# AMP_1_2.net
KiCad netlist of a schematic drawn in EAGLE
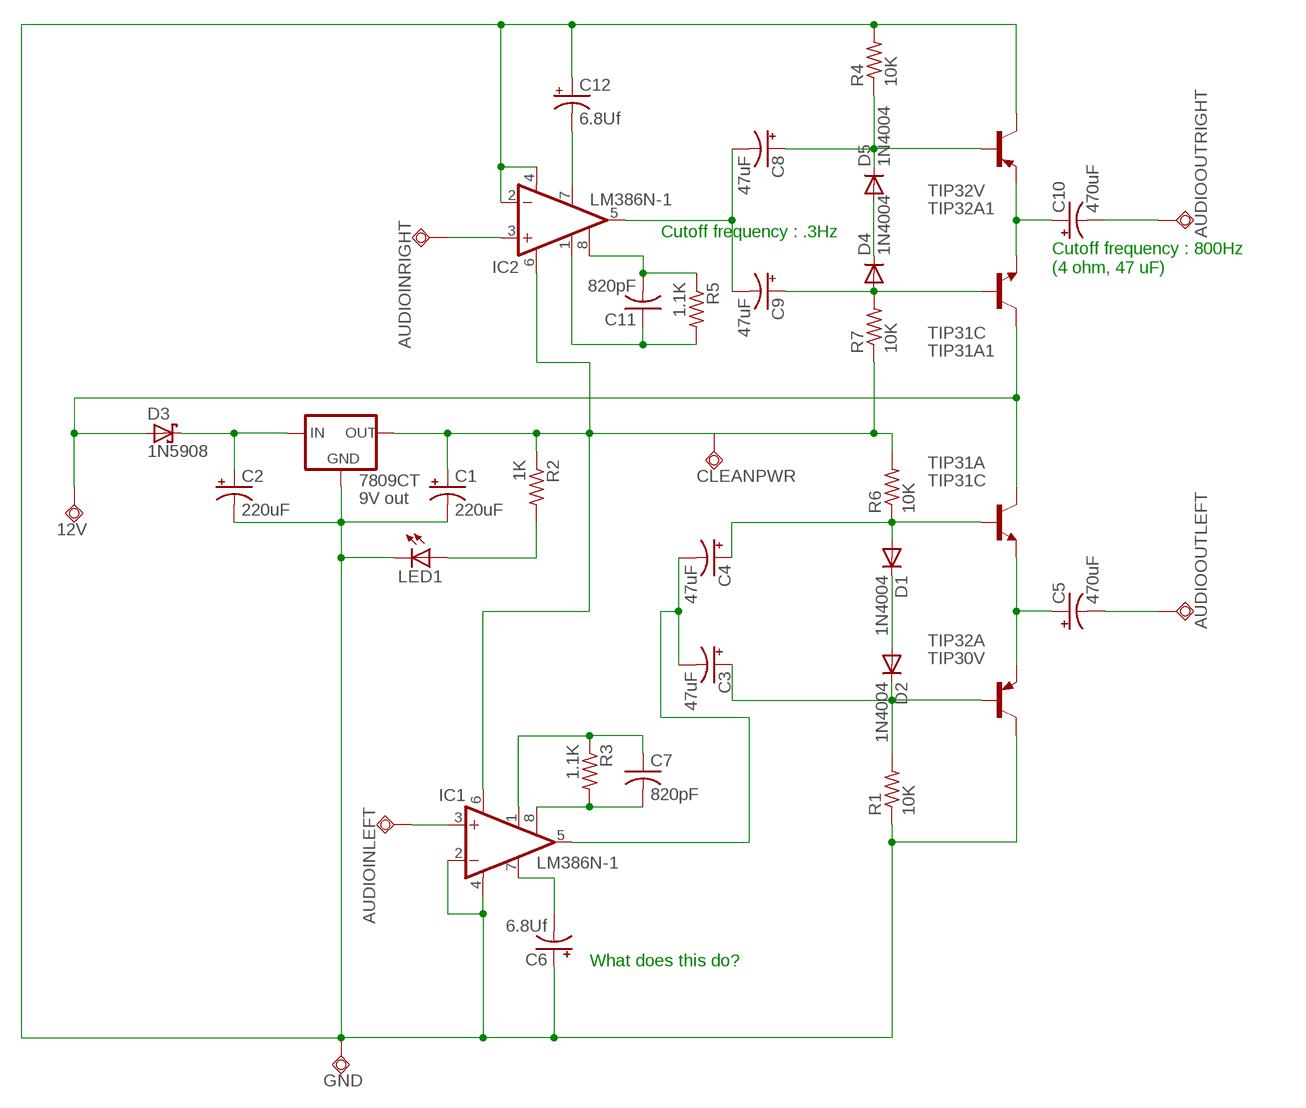
[diagram p0: schematic, sheet 1]

(export (version "E")
  (design (tool "Eeschema 10.0.6"))
  (components
    (comp (ref "12V")
      (value "TPSQPAD1-20")
      (footprint "eagle-import:P1-20")
      (libsource (lib "eagle-import") (part "TPSQPAD1-20"))
    )
    (comp (ref "7809CT")
      (value "9V out")
      (footprint "eagle-import:78XXS")
      (libsource (lib "eagle-import") (part "78XXS"))
    )
    (comp (ref "AUDIOINLEFT")
      (value "TPSQPAD1-20")
      (footprint "eagle-import:P1-20")
      (libsource (lib "eagle-import") (part "TPSQPAD1-20"))
    )
    (comp (ref "AUDIOINRIGHT")
      (value "TPSQPAD1-20")
      (footprint "eagle-import:P1-20")
      (libsource (lib "eagle-import") (part "TPSQPAD1-20"))
    )
    (comp (ref "AUDIOOUTLEFT")
      (value "TPSQPAD1-20")
      (footprint "eagle-import:P1-20")
      (libsource (lib "eagle-import") (part "TPSQPAD1-20"))
    )
    (comp (ref "AUDIOOUTRIGHT")
      (value "TPSQPAD1-20")
      (footprint "eagle-import:P1-20")
      (libsource (lib "eagle-import") (part "TPSQPAD1-20"))
    )
    (comp (ref "C1")
      (value "220uF")
      (footprint "eagle-import:B45181C")
      (libsource (lib "eagle-import") (part "CPOL-USB45181C"))
    )
    (comp (ref "C2")
      (value "220uF")
      (footprint "eagle-import:B45181C")
      (libsource (lib "eagle-import") (part "CPOL-USB45181C"))
    )
    (comp (ref "C3")
      (value "47uF")
      (footprint "eagle-import:E5-4")
      (libsource (lib "eagle-import") (part "CPOL-USE5-4"))
    )
    (comp (ref "C4")
      (value "47uF")
      (footprint "eagle-import:E5-4")
      (libsource (lib "eagle-import") (part "CPOL-USE5-4"))
    )
    (comp (ref "C5")
      (value "470uF")
      (footprint "eagle-import:E5-4")
      (libsource (lib "eagle-import") (part "CPOL-USE5-4"))
    )
    (comp (ref "C6")
      (value "6.8Uf")
      (footprint "eagle-import:E5-4")
      (libsource (lib "eagle-import") (part "CPOL-USE5-4"))
    )
    (comp (ref "C7")
      (value "820pF")
      (footprint "eagle-import:C050-050X075")
      (libsource (lib "eagle-import") (part "C-US050-050X075"))
    )
    (comp (ref "C8")
      (value "47uF")
      (footprint "eagle-import:E5-4")
      (libsource (lib "eagle-import") (part "CPOL-USE5-4"))
    )
    (comp (ref "C9")
      (value "47uF")
      (footprint "eagle-import:E5-4")
      (libsource (lib "eagle-import") (part "CPOL-USE5-4"))
    )
    (comp (ref "C10")
      (value "470uF")
      (footprint "eagle-import:E5-4")
      (libsource (lib "eagle-import") (part "CPOL-USE5-4"))
    )
    (comp (ref "C11")
      (value "820pF")
      (footprint "eagle-import:C050-050X075")
      (libsource (lib "eagle-import") (part "C-US050-050X075"))
    )
    (comp (ref "C12")
      (value "6.8Uf")
      (footprint "eagle-import:E5-4")
      (libsource (lib "eagle-import") (part "CPOL-USE5-4"))
    )
    (comp (ref "CLEANPWR")
      (value "TPSQPAD1-20")
      (footprint "eagle-import:P1-20")
      (libsource (lib "eagle-import") (part "TPSQPAD1-20"))
    )
    (comp (ref "D1")
      (value "1N4004")
      (footprint "eagle-import:DO41-10")
      (libsource (lib "eagle-import") (part "1N4004"))
    )
    (comp (ref "D2")
      (value "1N4004")
      (footprint "eagle-import:DO41-10")
      (libsource (lib "eagle-import") (part "1N4004"))
    )
    (comp (ref "D3")
      (value "1N5908")
      (footprint "eagle-import:C4111-15")
      (libsource (lib "eagle-import") (part "1N5908"))
    )
    (comp (ref "D4")
      (value "1N4004")
      (footprint "eagle-import:DO41-10")
      (libsource (lib "eagle-import") (part "1N4004"))
    )
    (comp (ref "D5")
      (value "1N4004")
      (footprint "eagle-import:DO41-10")
      (libsource (lib "eagle-import") (part "1N4004"))
    )
    (comp (ref "GND")
      (value "TPSQPAD1-20")
      (footprint "eagle-import:P1-20")
      (libsource (lib "eagle-import") (part "TPSQPAD1-20"))
    )
    (comp (ref "IC1")
      (value "LM386N-1")
      (footprint "eagle-import:DIL08")
      (libsource (lib "eagle-import") (part "LM386?-N1"))
    )
    (comp (ref "IC2")
      (value "LM386N-1")
      (footprint "eagle-import:DIL08")
      (libsource (lib "eagle-import") (part "LM386?-N1"))
    )
    (comp (ref "LED1")
      (value "LED5MM")
      (footprint "eagle-import:LED5MM")
      (libsource (lib "eagle-import") (part "LED5MM"))
    )
    (comp (ref "R1")
      (value "10K")
      (footprint "eagle-import:0204_7")
      (libsource (lib "eagle-import") (part "R-US_0204/7"))
    )
    (comp (ref "R2")
      (value "1K")
      (footprint "eagle-import:0204_7")
      (libsource (lib "eagle-import") (part "R-US_0204/7"))
    )
    (comp (ref "R3")
      (value "1.1K")
      (footprint "eagle-import:0204_7")
      (libsource (lib "eagle-import") (part "R-US_0204/7"))
    )
    (comp (ref "R4")
      (value "10K")
      (footprint "eagle-import:0204_7")
      (libsource (lib "eagle-import") (part "R-US_0204/7"))
    )
    (comp (ref "R5")
      (value "1.1K")
      (footprint "eagle-import:0204_7")
      (libsource (lib "eagle-import") (part "R-US_0204/7"))
    )
    (comp (ref "R6")
      (value "10K")
      (footprint "eagle-import:0204_7")
      (libsource (lib "eagle-import") (part "R-US_0204/7"))
    )
    (comp (ref "R7")
      (value "10K")
      (footprint "eagle-import:0204_7")
      (libsource (lib "eagle-import") (part "R-US_0204/7"))
    )
    (comp (ref "TIP31A")
      (value "TIP31C")
      (footprint "eagle-import:TO220V")
      (libsource (lib "eagle-import") (part "TIP31C"))
    )
    (comp (ref "TIP31A1")
      (value "TIP31C")
      (footprint "eagle-import:TO220V")
      (libsource (lib "eagle-import") (part "TIP31C"))
    )
    (comp (ref "TIP32A")
      (value "TIP30V")
      (footprint "eagle-import:TO220V")
      (libsource (lib "eagle-import") (part "TIP30V"))
    )
    (comp (ref "TIP32A1")
      (value "TIP32V")
      (footprint "eagle-import:TO220V")
      (libsource (lib "eagle-import") (part "TIP32V"))
    )
  )
  (nets
    (net (code "1") (name "Net-(7809CT-PadIN)") (class "Default")
      (node (ref "7809CT") (pin "IN") (pinfunction "IN_IN") (pintype "input"))
      (node (ref "C2") (pin "+") (pinfunction "+_+") (pintype "passive"))
      (node (ref "D3") (pin "C") (pinfunction "C_C") (pintype "passive"))
    )
    (net (code "2") (name "Net-(AUDIOOUTLEFT-PadTP)") (class "Default")
      (node (ref "AUDIOOUTLEFT") (pin "TP") (pinfunction "TP_TP") (pintype "input"))
      (node (ref "C5") (pin "-") (pinfunction "-_-") (pintype "passive"))
    )
    (net (code "3") (name "Net-(AUDIOOUTRIGHT-PadTP)") (class "Default")
      (node (ref "AUDIOOUTRIGHT") (pin "TP") (pinfunction "TP_TP") (pintype "input"))
      (node (ref "C10") (pin "-") (pinfunction "-_-") (pintype "passive"))
    )
    (net (code "4") (name "Net-(C7-Pad1)") (class "Default")
      (node (ref "C7") (pin "1") (pinfunction "1_1") (pintype "passive"))
      (node (ref "IC1") (pin "1") (pinfunction "GAIN_1") (pintype "passive"))
      (node (ref "R3") (pin "1") (pinfunction "1_1") (pintype "passive"))
    )
    (net (code "5") (name "Net-(C7-Pad2)") (class "Default")
      (node (ref "C7") (pin "2") (pinfunction "2_2") (pintype "passive"))
      (node (ref "IC1") (pin "8") (pinfunction "GAIN_8") (pintype "passive"))
      (node (ref "R3") (pin "2") (pinfunction "2_2") (pintype "passive"))
    )
    (net (code "6") (name "Net-(C11-Pad1)") (class "Default")
      (node (ref "C11") (pin "1") (pinfunction "1_1") (pintype "passive"))
      (node (ref "IC2") (pin "1") (pinfunction "GAIN_1") (pintype "passive"))
      (node (ref "R5") (pin "2") (pinfunction "2_2") (pintype "passive"))
    )
    (net (code "7") (name "Net-(C11-Pad2)") (class "Default")
      (node (ref "C11") (pin "2") (pinfunction "2_2") (pintype "passive"))
      (node (ref "IC2") (pin "8") (pinfunction "GAIN_8") (pintype "passive"))
      (node (ref "R5") (pin "1") (pinfunction "1_1") (pintype "passive"))
    )
    (net (code "8") (name "Net-(D1-PadC)") (class "Default")
      (node (ref "D1") (pin "C") (pinfunction "C_C") (pintype "passive"))
      (node (ref "D2") (pin "A") (pinfunction "A_A") (pintype "passive"))
    )
    (net (code "9") (name "Net-(D4-PadC)") (class "Default")
      (node (ref "D4") (pin "C") (pinfunction "C_C") (pintype "passive"))
      (node (ref "D5") (pin "A") (pinfunction "A_A") (pintype "passive"))
    )
    (net (code "10") (name "Net-(IC1-+IN)") (class "Default")
      (node (ref "AUDIOINLEFT") (pin "TP") (pinfunction "TP_TP") (pintype "input"))
      (node (ref "IC1") (pin "3") (pinfunction "+IN_3") (pintype "input"))
    )
    (net (code "11") (name "Net-(IC1--IN)") (class "Default")
      (node (ref "7809CT") (pin "GND") (pinfunction "GND_GND") (pintype "input"))
      (node (ref "C1") (pin "-") (pinfunction "-_-") (pintype "passive"))
      (node (ref "C12") (pin "+") (pinfunction "+_+") (pintype "passive"))
      (node (ref "C2") (pin "-") (pinfunction "-_-") (pintype "passive"))
      (node (ref "C6") (pin "+") (pinfunction "+_+") (pintype "passive"))
      (node (ref "GND") (pin "TP") (pinfunction "TP_TP") (pintype "input"))
      (node (ref "IC1") (pin "2") (pinfunction "-IN_2") (pintype "input"))
      (node (ref "IC1") (pin "4") (pinfunction "GND_4") (pintype "power_in"))
      (node (ref "IC2") (pin "2") (pinfunction "-IN_2") (pintype "input"))
      (node (ref "IC2") (pin "4") (pinfunction "GND_4") (pintype "power_in"))
      (node (ref "LED1") (pin "K") (pinfunction "C_K") (pintype "passive"))
      (node (ref "R1") (pin "1") (pinfunction "1_1") (pintype "passive"))
      (node (ref "R4") (pin "2") (pinfunction "2_2") (pintype "passive"))
      (node (ref "TIP32A") (pin "2") (pinfunction "C_2") (pintype "passive"))
      (node (ref "TIP32A1") (pin "2") (pinfunction "C_2") (pintype "passive"))
    )
    (net (code "12") (name "Net-(IC1-BYPASS)") (class "Default")
      (node (ref "C6") (pin "-") (pinfunction "-_-") (pintype "passive"))
      (node (ref "IC1") (pin "7") (pinfunction "BYPASS_7") (pintype "passive"))
    )
    (net (code "13") (name "Net-(IC1-OUT)") (class "Default")
      (node (ref "C3") (pin "-") (pinfunction "-_-") (pintype "passive"))
      (node (ref "C4") (pin "-") (pinfunction "-_-") (pintype "passive"))
      (node (ref "IC1") (pin "5") (pinfunction "OUT_5") (pintype "output"))
    )
    (net (code "14") (name "Net-(IC1-VS)") (class "Default")
      (node (ref "7809CT") (pin "OUT") (pinfunction "OUT_OUT") (pintype "passive"))
      (node (ref "C1") (pin "+") (pinfunction "+_+") (pintype "passive"))
      (node (ref "CLEANPWR") (pin "TP") (pinfunction "TP_TP") (pintype "input"))
      (node (ref "IC1") (pin "6") (pinfunction "VS_6") (pintype "power_in"))
      (node (ref "IC2") (pin "6") (pinfunction "VS_6") (pintype "power_in"))
      (node (ref "R2") (pin "1") (pinfunction "1_1") (pintype "passive"))
      (node (ref "R6") (pin "2") (pinfunction "2_2") (pintype "passive"))
      (node (ref "R7") (pin "1") (pinfunction "1_1") (pintype "passive"))
    )
    (net (code "15") (name "Net-(IC2-+IN)") (class "Default")
      (node (ref "AUDIOINRIGHT") (pin "TP") (pinfunction "TP_TP") (pintype "input"))
      (node (ref "IC2") (pin "3") (pinfunction "+IN_3") (pintype "input"))
    )
    (net (code "16") (name "Net-(IC2-BYPASS)") (class "Default")
      (node (ref "C12") (pin "-") (pinfunction "-_-") (pintype "passive"))
      (node (ref "IC2") (pin "7") (pinfunction "BYPASS_7") (pintype "passive"))
    )
    (net (code "17") (name "Net-(IC2-OUT)") (class "Default")
      (node (ref "C8") (pin "-") (pinfunction "-_-") (pintype "passive"))
      (node (ref "C9") (pin "-") (pinfunction "-_-") (pintype "passive"))
      (node (ref "IC2") (pin "5") (pinfunction "OUT_5") (pintype "output"))
    )
    (net (code "18") (name "Net-(LED1-PadA)") (class "Default")
      (node (ref "LED1") (pin "A") (pinfunction "A_A") (pintype "passive"))
      (node (ref "R2") (pin "2") (pinfunction "2_2") (pintype "passive"))
    )
    (net (code "19") (name "Net-(TIP31A-B)") (class "Default")
      (node (ref "C4") (pin "+") (pinfunction "+_+") (pintype "passive"))
      (node (ref "D1") (pin "A") (pinfunction "A_A") (pintype "passive"))
      (node (ref "R6") (pin "1") (pinfunction "1_1") (pintype "passive"))
      (node (ref "TIP31A") (pin "1") (pinfunction "B_1") (pintype "passive"))
    )
    (net (code "20") (name "Net-(TIP31A-C)") (class "Default")
      (node (ref "12V") (pin "TP") (pinfunction "TP_TP") (pintype "input"))
      (node (ref "D3") (pin "A") (pinfunction "A_A") (pintype "passive"))
      (node (ref "TIP31A") (pin "2") (pinfunction "C_2") (pintype "passive"))
      (node (ref "TIP31A1") (pin "2") (pinfunction "C_2") (pintype "passive"))
    )
    (net (code "21") (name "Net-(TIP31A-E)") (class "Default")
      (node (ref "C5") (pin "+") (pinfunction "+_+") (pintype "passive"))
      (node (ref "TIP31A") (pin "3") (pinfunction "E_3") (pintype "passive"))
      (node (ref "TIP32A") (pin "3") (pinfunction "E_3") (pintype "passive"))
    )
    (net (code "22") (name "Net-(TIP31A1-B)") (class "Default")
      (node (ref "C9") (pin "+") (pinfunction "+_+") (pintype "passive"))
      (node (ref "D4") (pin "A") (pinfunction "A_A") (pintype "passive"))
      (node (ref "R7") (pin "2") (pinfunction "2_2") (pintype "passive"))
      (node (ref "TIP31A1") (pin "1") (pinfunction "B_1") (pintype "passive"))
    )
    (net (code "23") (name "Net-(TIP31A1-E)") (class "Default")
      (node (ref "C10") (pin "+") (pinfunction "+_+") (pintype "passive"))
      (node (ref "TIP31A1") (pin "3") (pinfunction "E_3") (pintype "passive"))
      (node (ref "TIP32A1") (pin "3") (pinfunction "E_3") (pintype "passive"))
    )
    (net (code "24") (name "Net-(TIP32A-B)") (class "Default")
      (node (ref "C3") (pin "+") (pinfunction "+_+") (pintype "passive"))
      (node (ref "D2") (pin "C") (pinfunction "C_C") (pintype "passive"))
      (node (ref "R1") (pin "2") (pinfunction "2_2") (pintype "passive"))
      (node (ref "TIP32A") (pin "1") (pinfunction "B_1") (pintype "passive"))
    )
    (net (code "25") (name "Net-(TIP32A1-B)") (class "Default")
      (node (ref "C8") (pin "+") (pinfunction "+_+") (pintype "passive"))
      (node (ref "D5") (pin "C") (pinfunction "C_C") (pintype "passive"))
      (node (ref "R4") (pin "1") (pinfunction "1_1") (pintype "passive"))
      (node (ref "TIP32A1") (pin "1") (pinfunction "B_1") (pintype "passive"))
    )
  )
)
